# 12_-_POWER.net
KiCad netlist of a schematic drawn in Altium Designer
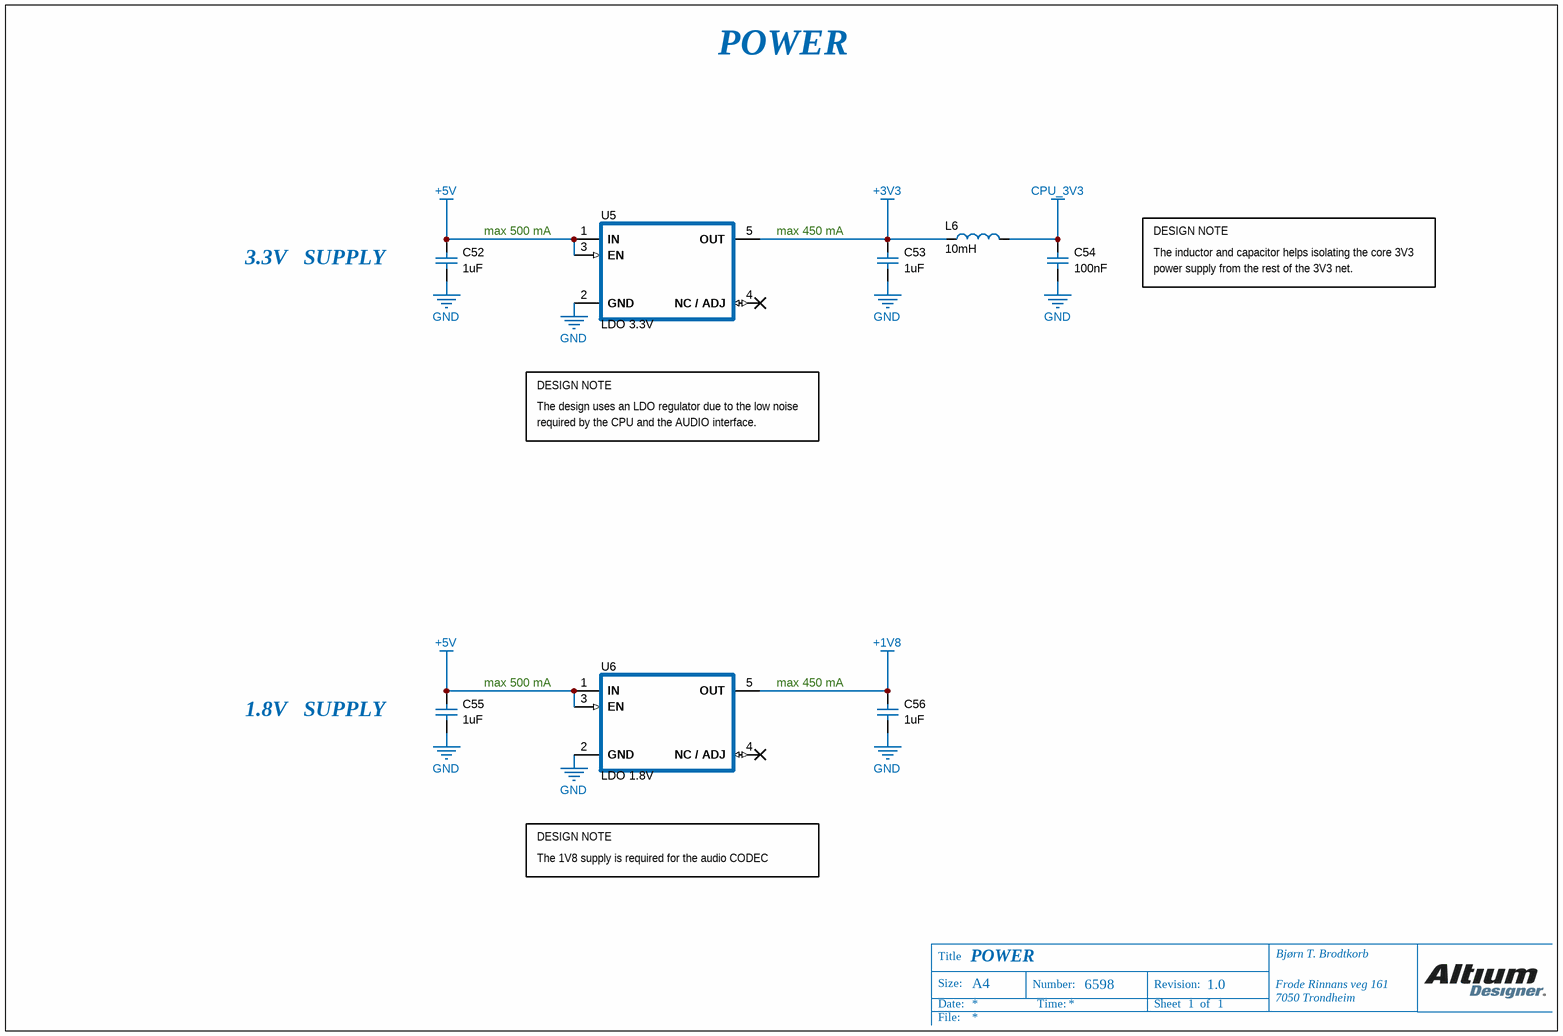
[diagram p0: [12] - POWER.SchDoc]

(export (version "E")
  (design (tool "Eeschema 10.0.6"))
  (components
    (comp (ref "C52")
      (value "1uF")
      (footprint "C0805")
      (description "C0805")
      (fields (field (name "Comment") "08053C105KAT2A"))
      (libsource (lib "Passive components") (part "08053C105KAT2A"))
    )
    (comp (ref "C53")
      (value "1uF")
      (footprint "C0805")
      (description "C0805")
      (fields (field (name "Comment") "08053C105KAT2A"))
      (libsource (lib "Passive components") (part "08053C105KAT2A"))
    )
    (comp (ref "C54")
      (value "100nF")
      (footprint "C0603")
      (description "C0603")
      (fields (field (name "Comment") "02016D104KAT2A"))
      (libsource (lib "Passive components") (part "02016D104KAT2A"))
    )
    (comp (ref "C55")
      (value "1uF")
      (footprint "C0805")
      (description "C0805")
      (fields (field (name "Comment") "08053C105KAT2A"))
      (libsource (lib "Passive components") (part "08053C105KAT2A"))
    )
    (comp (ref "C56")
      (value "1uF")
      (footprint "C0805")
      (description "C0805")
      (fields (field (name "Comment") "08053C105KAT2A"))
      (libsource (lib "Passive components") (part "08053C105KAT2A"))
    )
    (comp (ref "L6")
      (value "10mH")
      (footprint "Inductor 0603")
      (description "Inductor 0603")
      (fields (field (name "Comment") "MLZ1608A2R2WT"))
      (libsource (lib "Passive components") (part "MLZ1608A2R2WT"))
    )
    (comp (ref "U5")
      (value "LDO 3.3V")
      (footprint "NCV8161BSN330T1G")
      (description "LDO fixed 3.3V 450mA ultra-low noise")
      (libsource (lib "Voltage regulators") (part "NCV8161BSN330T1G"))
    )
    (comp (ref "U6")
      (value "LDO 1.8V")
      (footprint "SOT95P275X110-5N")
      (description "LDO fixed 1.8V 450mA ultra-low noise")
      (libsource (lib "Voltage regulators") (part "NCV8161ASN180T1G"))
    )
  )
  (nets
    (net (code "1") (name "+1V8") (class "Default")
      (node (ref "C56") (pin "2") (pinfunction "2_2") (pintype "passive"))
      (node (ref "U6") (pin "5") (pinfunction "OUT_5") (pintype "power_in"))
    )
    (net (code "2") (name "+3V3") (class "Default")
      (node (ref "C53") (pin "2") (pinfunction "2_2") (pintype "passive"))
      (node (ref "L6") (pin "1") (pinfunction "1_1") (pintype "passive"))
      (node (ref "U5") (pin "5") (pinfunction "OUT_5") (pintype "power_in"))
    )
    (net (code "3") (name "+5V") (class "Default")
      (node (ref "C52") (pin "2") (pinfunction "2_2") (pintype "passive"))
      (node (ref "C55") (pin "2") (pinfunction "2_2") (pintype "passive"))
      (node (ref "U5") (pin "1") (pinfunction "IN_1") (pintype "power_in"))
      (node (ref "U5") (pin "3") (pinfunction "EN_3") (pintype "input"))
      (node (ref "U6") (pin "1") (pinfunction "IN_1") (pintype "power_in"))
      (node (ref "U6") (pin "3") (pinfunction "EN_3") (pintype "input"))
    )
    (net (code "4") (name "CPU_3V3") (class "Default")
      (node (ref "C54") (pin "2") (pinfunction "2_2") (pintype "passive"))
      (node (ref "L6") (pin "2") (pinfunction "2_2") (pintype "passive"))
    )
    (net (code "5") (name "GND") (class "Default")
      (node (ref "C52") (pin "1") (pinfunction "1_1") (pintype "passive"))
      (node (ref "C53") (pin "1") (pinfunction "1_1") (pintype "passive"))
      (node (ref "C54") (pin "1") (pinfunction "1_1") (pintype "passive"))
      (node (ref "C55") (pin "1") (pinfunction "1_1") (pintype "passive"))
      (node (ref "C56") (pin "1") (pinfunction "1_1") (pintype "passive"))
      (node (ref "U5") (pin "2") (pinfunction "GND_2") (pintype "power_in"))
      (node (ref "U6") (pin "2") (pinfunction "GND_2") (pintype "power_in"))
    )
    (net (code "6") (name "unconnected-(U5-NC_{slash}_ADJ-Pad4)") (class "Default")
      (node (ref "U5") (pin "4") (pinfunction "NC_/_ADJ_4") (pintype "bidirectional+no_connect"))
    )
    (net (code "7") (name "unconnected-(U6-NC_{slash}_ADJ-Pad4)") (class "Default")
      (node (ref "U6") (pin "4") (pinfunction "NC_/_ADJ_4") (pintype "bidirectional+no_connect"))
    )
  )
)
